# Transistors.net
KiCad netlist of a schematic drawn in Altium Designer
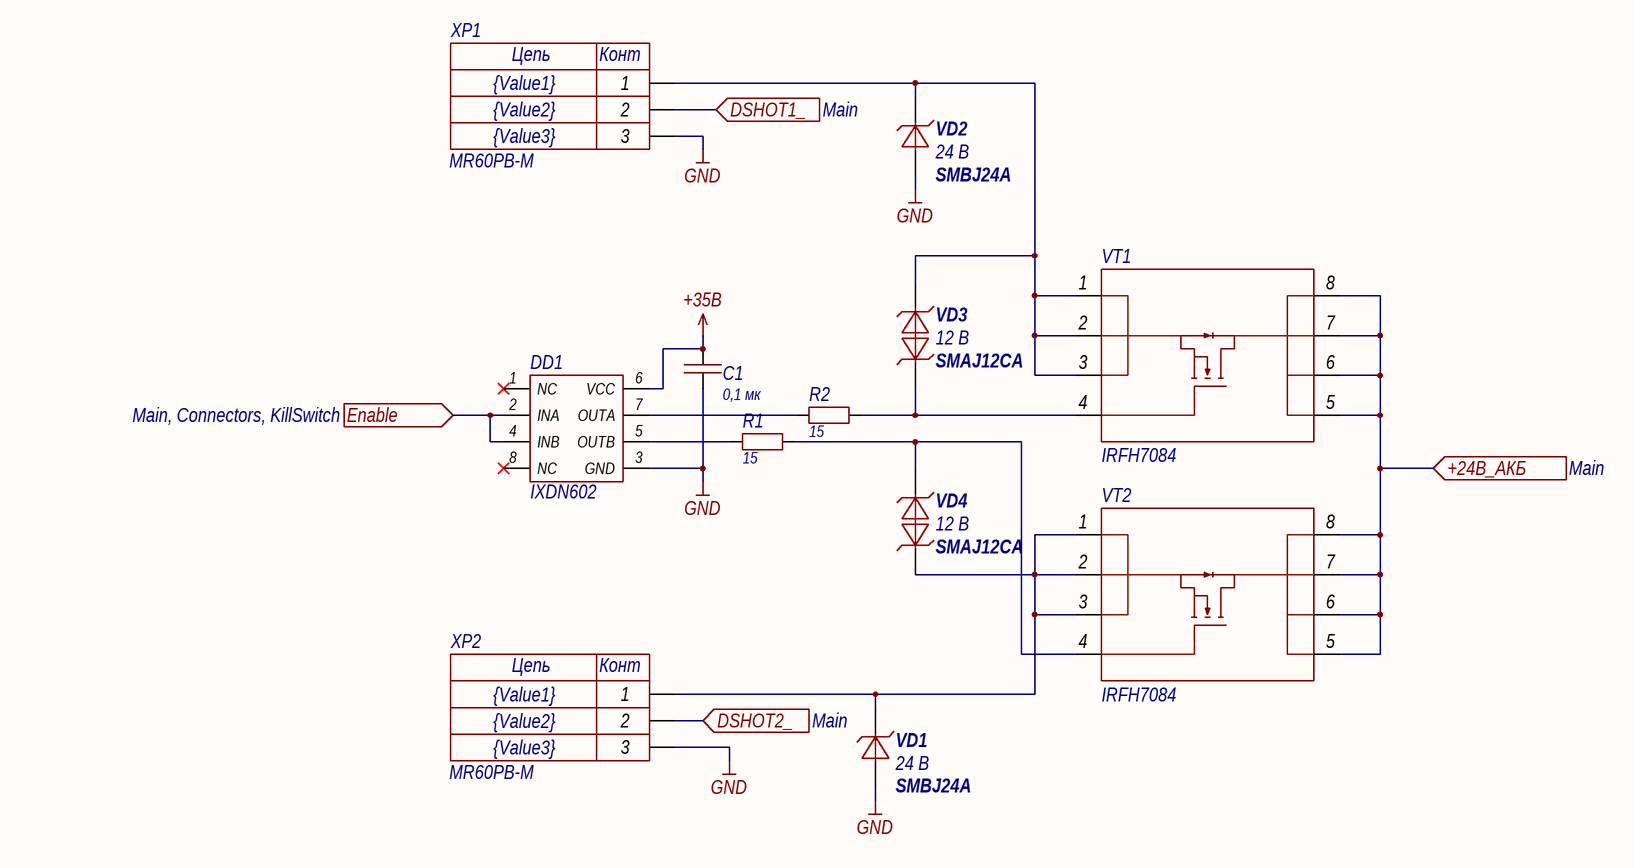
[diagram p0: Transistors.SchDoc]

(export (version "E")
  (design (tool "Eeschema 10.0.6"))
  (components
    (comp (ref "C1")
      (value "0,1 мк")
      (footprint "0603C")
      (description "Конденсатор")
      (fields (field (name "PART NUMBER") "Capacitor_0,1u_10_50V_X7R_0603C") (field (name "TOLERANCE") "0,1"))
      (libsource (lib "Hydrolib") (part "Capacitor"))
    )
    (comp (ref "DD1")
      (value "IXDN602")
      (footprint "SOIC-8")
      (description "Двухканальный драйвер затвора для mosfet и igbt транзисторов")
      (libsource (lib "Hydrolib") (part "IXDN602"))
    )
    (comp (ref "R1")
      (value "15")
      (footprint "0603R")
      (description "Резистор номиналом 15 Ом 1%")
      (fields (field (name "PART NUMBER") "Resistor_15_1_0603") (field (name "TOLERANCE") "1%"))
      (libsource (lib "Hydrolib") (part "Resistor"))
    )
    (comp (ref "R2")
      (value "15")
      (footprint "0603R")
      (description "Резистор номиналом 15 Ом 1%")
      (fields (field (name "PART NUMBER") "Resistor_15_1_0603") (field (name "TOLERANCE") "1%"))
      (libsource (lib "Hydrolib") (part "Resistor"))
    )
    (comp (ref "VD1")
      (value "SMBJ24A")
      (footprint "SMB")
      (description "Защитный диод на 24 В, рассеиваемая мощность 600 Вт")
      (fields (field (name "ALTIUM_VALUE") "24 В"))
      (libsource (lib "Hydrolib") (part "TVS_1_1dir"))
    )
    (comp (ref "VD2")
      (value "SMBJ24A")
      (footprint "SMB")
      (description "Защитный диод на 24 В, рассеиваемая мощность 600 Вт")
      (fields (field (name "ALTIUM_VALUE") "24 В"))
      (libsource (lib "Hydrolib") (part "TVS_1_1dir"))
    )
    (comp (ref "VD3")
      (value "SMAJ12CA")
      (footprint "SMA")
      (description "Защитный диод на 12 В, рассеиваемая мощность 400 Вт")
      (fields (field (name "ALTIUM_VALUE") "12 В"))
      (libsource (lib "Hydrolib") (part "TVS_1_2dir"))
    )
    (comp (ref "VD4")
      (value "SMAJ12CA")
      (footprint "SMA")
      (description "Защитный диод на 12 В, рассеиваемая мощность 400 Вт")
      (fields (field (name "ALTIUM_VALUE") "12 В"))
      (libsource (lib "Hydrolib") (part "TVS_1_2dir"))
    )
    (comp (ref "VT1")
      (value "IRFH7084")
      (footprint "PQFN_5x6")
      (description "N-канальный MOSFET")
      (libsource (lib "Hydrolib") (part "MOSFET_N-channel_8pin"))
    )
    (comp (ref "VT2")
      (value "IRFH7084")
      (footprint "PQFN_5x6")
      (description "N-канальный MOSFET")
      (libsource (lib "Hydrolib") (part "MOSFET_N-channel_8pin"))
    )
    (comp (ref "XP1")
      (value "MR60PB-M")
      (footprint "MR60PB-M")
      (description "60 А (40 продолжительно), 3 контакта, прямой отец")
      (fields
        (field (name "VALUE3") "{Value3}")
        (field (name "VALUE2") "{Value2}")
        (field (name "VALUE1") "{Value1}")
      )
      (libsource (lib "Hydrolib") (part "Conn_3pin"))
    )
    (comp (ref "XP2")
      (value "MR60PB-M")
      (footprint "MR60PB-M")
      (description "60 А (40 продолжительно), 3 контакта, прямой отец")
      (fields
        (field (name "VALUE3") "{Value3}")
        (field (name "VALUE2") "{Value2}")
        (field (name "VALUE1") "{Value1}")
      )
      (libsource (lib "Hydrolib") (part "Conn_3pin"))
    )
  )
  (nets
    (net (code "1") (name "+35В") (class "Default")
      (node (ref "C1") (pin "2") (pinfunction "2_2") (pintype "passive"))
      (node (ref "DD1") (pin "6") (pinfunction "VCC_6") (pintype "passive"))
    )
    (net (code "2") (name "/+24В_АКБ") (class "Default")
      (node (ref "VT1") (pin "5") (pinfunction "5_5") (pintype "passive"))
      (node (ref "VT1") (pin "6") (pinfunction "6_6") (pintype "passive"))
      (node (ref "VT1") (pin "7") (pinfunction "7_7") (pintype "passive"))
      (node (ref "VT1") (pin "8") (pinfunction "8_8") (pintype "passive"))
      (node (ref "VT2") (pin "5") (pinfunction "5_5") (pintype "passive"))
      (node (ref "VT2") (pin "6") (pinfunction "6_6") (pintype "passive"))
      (node (ref "VT2") (pin "7") (pinfunction "7_7") (pintype "passive"))
      (node (ref "VT2") (pin "8") (pinfunction "8_8") (pintype "passive"))
    )
    (net (code "3") (name "/DSHOT1_") (class "Default")
      (node (ref "XP1") (pin "2") (pinfunction "2_2") (pintype "passive"))
    )
    (net (code "4") (name "/DSHOT2_") (class "Default")
      (node (ref "XP2") (pin "2") (pinfunction "2_2") (pintype "passive"))
    )
    (net (code "5") (name "/Enable") (class "Default")
      (node (ref "DD1") (pin "2") (pinfunction "INA_2") (pintype "passive"))
      (node (ref "DD1") (pin "4") (pinfunction "INB_4") (pintype "passive"))
    )
    (net (code "6") (name "GND") (class "Default")
      (node (ref "C1") (pin "1") (pinfunction "1_1") (pintype "passive"))
      (node (ref "DD1") (pin "3") (pinfunction "GND_3") (pintype "passive"))
      (node (ref "VD1") (pin "1") (pinfunction "1_1") (pintype "passive"))
      (node (ref "VD2") (pin "1") (pinfunction "1_1") (pintype "passive"))
      (node (ref "XP1") (pin "3") (pinfunction "3_3") (pintype "passive"))
      (node (ref "XP2") (pin "3") (pinfunction "3_3") (pintype "passive"))
    )
    (net (code "7") (name "Net-(DD1-OUTA)") (class "Default")
      (node (ref "DD1") (pin "7") (pinfunction "OUTA_7") (pintype "passive"))
      (node (ref "R2") (pin "1") (pinfunction "1_1") (pintype "passive"))
    )
    (net (code "8") (name "Net-(DD1-OUTB)") (class "Default")
      (node (ref "DD1") (pin "5") (pinfunction "OUTB_5") (pintype "passive"))
      (node (ref "R1") (pin "1") (pinfunction "1_1") (pintype "passive"))
    )
    (net (code "9") (name "Net-(R1-Pad2)") (class "Default")
      (node (ref "R1") (pin "2") (pinfunction "2_2") (pintype "passive"))
      (node (ref "VD4") (pin "2") (pinfunction "2_2") (pintype "passive"))
      (node (ref "VT2") (pin "4") (pinfunction "4_4") (pintype "passive"))
    )
    (net (code "10") (name "Net-(R2-Pad2)") (class "Default")
      (node (ref "R2") (pin "2") (pinfunction "2_2") (pintype "passive"))
      (node (ref "VD3") (pin "1") (pinfunction "1_1") (pintype "passive"))
      (node (ref "VT1") (pin "4") (pinfunction "4_4") (pintype "passive"))
    )
    (net (code "11") (name "Net-(VD1-Pad2)") (class "Default")
      (node (ref "VD1") (pin "2") (pinfunction "2_2") (pintype "passive"))
      (node (ref "VD4") (pin "1") (pinfunction "1_1") (pintype "passive"))
      (node (ref "VT2") (pin "1") (pinfunction "1_1") (pintype "passive"))
      (node (ref "VT2") (pin "2") (pinfunction "2_2") (pintype "passive"))
      (node (ref "VT2") (pin "3") (pinfunction "3_3") (pintype "passive"))
      (node (ref "XP2") (pin "1") (pinfunction "1_1") (pintype "passive"))
    )
    (net (code "12") (name "Net-(VD2-Pad2)") (class "Default")
      (node (ref "VD2") (pin "2") (pinfunction "2_2") (pintype "passive"))
      (node (ref "VD3") (pin "2") (pinfunction "2_2") (pintype "passive"))
      (node (ref "VT1") (pin "1") (pinfunction "1_1") (pintype "passive"))
      (node (ref "VT1") (pin "2") (pinfunction "2_2") (pintype "passive"))
      (node (ref "VT1") (pin "3") (pinfunction "3_3") (pintype "passive"))
      (node (ref "XP1") (pin "1") (pinfunction "1_1") (pintype "passive"))
    )
    (net (code "13") (name "unconnected-(DD1-NC-Pad1)") (class "Default")
      (node (ref "DD1") (pin "1") (pinfunction "NC_1") (pintype "passive+no_connect"))
    )
    (net (code "14") (name "unconnected-(DD1-NC-Pad8)") (class "Default")
      (node (ref "DD1") (pin "8") (pinfunction "NC_8") (pintype "passive+no_connect"))
    )
  )
)
